# RGB_Matrix.net
KiCad netlist of a schematic drawn in EAGLE
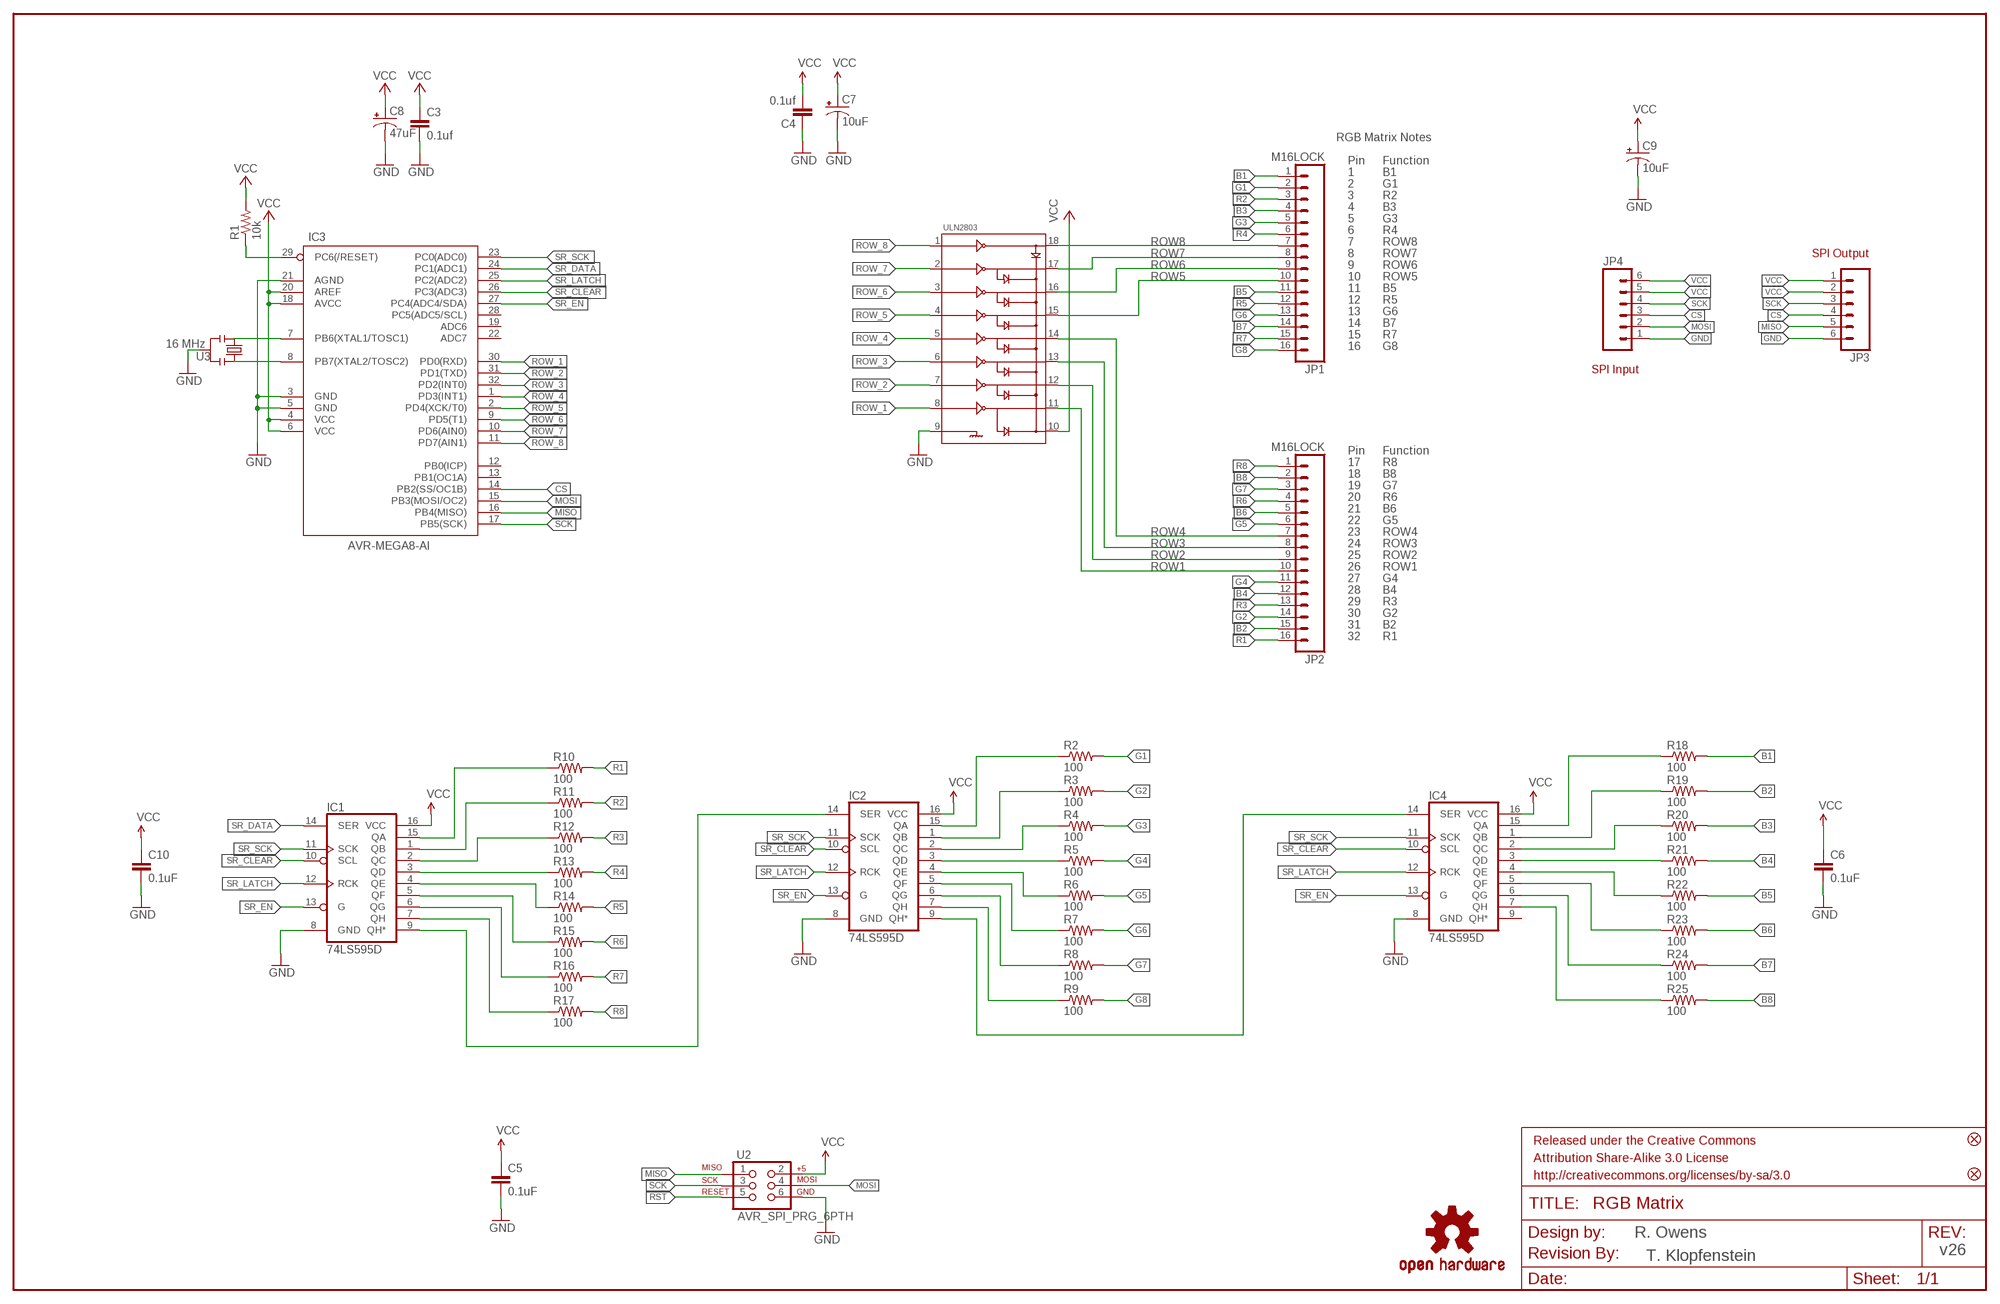
[diagram p0: schematic, sheet 1]

(export (version "E")
  (design (tool "Eeschema 10.0.6"))
  (components
    (comp (ref "C3")
      (value "0.1uf")
      (footprint "eagle-import:0603-CAP")
      (libsource (lib "eagle-import") (part "CAP0603-CAP"))
    )
    (comp (ref "C4")
      (value "0.1uf")
      (footprint "eagle-import:0603-CAP")
      (libsource (lib "eagle-import") (part "CAP0603-CAP"))
    )
    (comp (ref "C5")
      (value "0.1uF")
      (footprint "eagle-import:0603-CAP")
      (libsource (lib "eagle-import") (part "CAP0603-CAP"))
    )
    (comp (ref "C6")
      (value "0.1uF")
      (footprint "eagle-import:0603-CAP")
      (libsource (lib "eagle-import") (part "CAP0603-CAP"))
    )
    (comp (ref "C7")
      (value "10uF")
      (footprint "eagle-import:EIA3216")
      (libsource (lib "eagle-import") (part "CAP_POL1206"))
    )
    (comp (ref "C8")
      (value "47uF")
      (footprint "eagle-import:EIA3528")
      (libsource (lib "eagle-import") (part "CAP_POL3528"))
    )
    (comp (ref "C9")
      (value "10uF")
      (footprint "eagle-import:EIA3216")
      (libsource (lib "eagle-import") (part "CAP_POL1206"))
    )
    (comp (ref "C10")
      (value "0.1uF")
      (footprint "eagle-import:0603-CAP")
      (libsource (lib "eagle-import") (part "CAP0603-CAP"))
    )
    (comp (ref "FRAME1")
      (value "FRAME-LEDGER")
      (footprint "eagle-import:CREATIVE_COMMONS")
      (libsource (lib "eagle-import") (part "FRAME-LEDGER"))
    )
    (comp (ref "IC1")
      (value "74LS595D")
      (footprint "eagle-import:SO16")
      (libsource (lib "eagle-import") (part "74595DLS"))
    )
    (comp (ref "IC2")
      (value "74LS595D")
      (footprint "eagle-import:SO16")
      (libsource (lib "eagle-import") (part "74595DLS"))
    )
    (comp (ref "IC3")
      (value "AVR-MEGA8-AI")
      (footprint "eagle-import:TQFP32-08")
      (libsource (lib "eagle-import") (part "AVR-MEGA8-AI"))
    )
    (comp (ref "IC4")
      (value "74LS595D")
      (footprint "eagle-import:SO16")
      (libsource (lib "eagle-import") (part "74595DLS"))
    )
    (comp (ref "JP1")
      (value "M16LOCK")
      (footprint "eagle-import:1X16_LOCK")
      (libsource (lib "eagle-import") (part "M16LOCK"))
    )
    (comp (ref "JP2")
      (value "M16LOCK")
      (footprint "eagle-import:1X16_LOCK")
      (libsource (lib "eagle-import") (part "M16LOCK"))
    )
    (comp (ref "JP3")
      (value "M06SMD")
      (footprint "eagle-import:1X06-SMD")
      (libsource (lib "eagle-import") (part "M06SMD"))
    )
    (comp (ref "JP4")
      (value "M06LOCK")
      (footprint "eagle-import:1X06_LOCK")
      (libsource (lib "eagle-import") (part "SparkFun-Connectors_M06LOCK"))
    )
    (comp (ref "LOGO1")
      (value "OSHW-LOGOL")
      (footprint "eagle-import:OSHW-LOGO-L")
      (libsource (lib "eagle-import") (part "OSHW-LOGOL"))
    )
    (comp (ref "R1")
      (value "10k")
      (footprint "eagle-import:0603-RES")
      (libsource (lib "eagle-import") (part "RESISTOR0603-RES"))
    )
    (comp (ref "R2")
      (value "100")
      (footprint "eagle-import:0603-RES")
      (libsource (lib "eagle-import") (part "RESISTOR0603-RES"))
    )
    (comp (ref "R3")
      (value "100")
      (footprint "eagle-import:0603-RES")
      (libsource (lib "eagle-import") (part "RESISTOR0603-RES"))
    )
    (comp (ref "R4")
      (value "100")
      (footprint "eagle-import:0603-RES")
      (libsource (lib "eagle-import") (part "RESISTOR0603-RES"))
    )
    (comp (ref "R5")
      (value "100")
      (footprint "eagle-import:0603-RES")
      (libsource (lib "eagle-import") (part "RESISTOR0603-RES"))
    )
    (comp (ref "R6")
      (value "100")
      (footprint "eagle-import:0603-RES")
      (libsource (lib "eagle-import") (part "RESISTOR0603-RES"))
    )
    (comp (ref "R7")
      (value "100")
      (footprint "eagle-import:0603-RES")
      (libsource (lib "eagle-import") (part "RESISTOR0603-RES"))
    )
    (comp (ref "R8")
      (value "100")
      (footprint "eagle-import:0603-RES")
      (libsource (lib "eagle-import") (part "RESISTOR0603-RES"))
    )
    (comp (ref "R9")
      (value "100")
      (footprint "eagle-import:0603-RES")
      (libsource (lib "eagle-import") (part "RESISTOR0603-RES"))
    )
    (comp (ref "R10")
      (value "100")
      (footprint "eagle-import:0603-RES")
      (libsource (lib "eagle-import") (part "RESISTOR0603-RES"))
    )
    (comp (ref "R11")
      (value "100")
      (footprint "eagle-import:0603-RES")
      (libsource (lib "eagle-import") (part "RESISTOR0603-RES"))
    )
    (comp (ref "R12")
      (value "100")
      (footprint "eagle-import:0603-RES")
      (libsource (lib "eagle-import") (part "RESISTOR0603-RES"))
    )
    (comp (ref "R13")
      (value "100")
      (footprint "eagle-import:0603-RES")
      (libsource (lib "eagle-import") (part "RESISTOR0603-RES"))
    )
    (comp (ref "R14")
      (value "100")
      (footprint "eagle-import:0603-RES")
      (libsource (lib "eagle-import") (part "RESISTOR0603-RES"))
    )
    (comp (ref "R15")
      (value "100")
      (footprint "eagle-import:0603-RES")
      (libsource (lib "eagle-import") (part "RESISTOR0603-RES"))
    )
    (comp (ref "R16")
      (value "100")
      (footprint "eagle-import:0603-RES")
      (libsource (lib "eagle-import") (part "RESISTOR0603-RES"))
    )
    (comp (ref "R17")
      (value "100")
      (footprint "eagle-import:0603-RES")
      (libsource (lib "eagle-import") (part "RESISTOR0603-RES"))
    )
    (comp (ref "R18")
      (value "100")
      (footprint "eagle-import:0603-RES")
      (libsource (lib "eagle-import") (part "RESISTOR0603-RES"))
    )
    (comp (ref "R19")
      (value "100")
      (footprint "eagle-import:0603-RES")
      (libsource (lib "eagle-import") (part "RESISTOR0603-RES"))
    )
    (comp (ref "R20")
      (value "100")
      (footprint "eagle-import:0603-RES")
      (libsource (lib "eagle-import") (part "RESISTOR0603-RES"))
    )
    (comp (ref "R21")
      (value "100")
      (footprint "eagle-import:0603-RES")
      (libsource (lib "eagle-import") (part "RESISTOR0603-RES"))
    )
    (comp (ref "R22")
      (value "100")
      (footprint "eagle-import:0603-RES")
      (libsource (lib "eagle-import") (part "RESISTOR0603-RES"))
    )
    (comp (ref "R23")
      (value "100")
      (footprint "eagle-import:0603-RES")
      (libsource (lib "eagle-import") (part "RESISTOR0603-RES"))
    )
    (comp (ref "R24")
      (value "100")
      (footprint "eagle-import:0603-RES")
      (libsource (lib "eagle-import") (part "RESISTOR0603-RES"))
    )
    (comp (ref "R25")
      (value "100")
      (footprint "eagle-import:0603-RES")
      (libsource (lib "eagle-import") (part "RESISTOR0603-RES"))
    )
    (comp (ref "U$1")
      (value "FIDUCIAL1X2")
      (footprint "eagle-import:FIDUCIAL-1X2")
      (libsource (lib "eagle-import") (part "FIDUCIAL1X2"))
    )
    (comp (ref "U$2")
      (value "REVISION")
      (footprint "eagle-import:REVISION")
      (libsource (lib "eagle-import") (part "REVISION"))
    )
    (comp (ref "U$3")
      (value "FIDUCIAL1X2")
      (footprint "eagle-import:FIDUCIAL-1X2")
      (libsource (lib "eagle-import") (part "FIDUCIAL1X2"))
    )
    (comp (ref "U2")
      (value "AVR_SPI_PRG_6PTH")
      (footprint "eagle-import:2X3")
      (libsource (lib "eagle-import") (part "AVR_SPI_PRG_6PTH"))
    )
    (comp (ref "U3")
      (value "16 MHz")
      (footprint "eagle-import:RESONATOR-SMD")
      (libsource (lib "eagle-import") (part "RESONATORSMD"))
    )
    (comp (ref "ULN2803")
      (value "ULN2803SOICW")
      (footprint "eagle-import:SO18L")
      (libsource (lib "eagle-import") (part "ULN2803SOICW"))
    )
  )
  (nets
    (net (code "1") (name "/ROW1") (class "Default")
      (node (ref "JP2") (pin "10") (pinfunction "10_10") (pintype "passive"))
      (node (ref "ULN2803") (pin "11") (pinfunction "11_11") (pintype "bidirectional"))
    )
    (net (code "2") (name "/ROW2") (class "Default")
      (node (ref "JP2") (pin "9") (pinfunction "9_9") (pintype "passive"))
      (node (ref "ULN2803") (pin "12") (pinfunction "12_12") (pintype "bidirectional"))
    )
    (net (code "3") (name "/ROW3") (class "Default")
      (node (ref "JP2") (pin "8") (pinfunction "8_8") (pintype "passive"))
      (node (ref "ULN2803") (pin "13") (pinfunction "13_13") (pintype "bidirectional"))
    )
    (net (code "4") (name "/ROW4") (class "Default")
      (node (ref "JP2") (pin "7") (pinfunction "7_7") (pintype "passive"))
      (node (ref "ULN2803") (pin "14") (pinfunction "14_14") (pintype "bidirectional"))
    )
    (net (code "5") (name "/ROW5") (class "Default")
      (node (ref "JP1") (pin "10") (pinfunction "10_10") (pintype "passive"))
      (node (ref "ULN2803") (pin "15") (pinfunction "15_15") (pintype "bidirectional"))
    )
    (net (code "6") (name "/ROW6") (class "Default")
      (node (ref "JP1") (pin "9") (pinfunction "9_9") (pintype "passive"))
      (node (ref "ULN2803") (pin "16") (pinfunction "16_16") (pintype "bidirectional"))
    )
    (net (code "7") (name "/ROW7") (class "Default")
      (node (ref "JP1") (pin "8") (pinfunction "8_8") (pintype "passive"))
      (node (ref "ULN2803") (pin "17") (pinfunction "17_17") (pintype "bidirectional"))
    )
    (net (code "8") (name "/ROW8") (class "Default")
      (node (ref "JP1") (pin "7") (pinfunction "7_7") (pintype "passive"))
      (node (ref "ULN2803") (pin "18") (pinfunction "18_18") (pintype "bidirectional"))
    )
    (net (code "9") (name "B1") (class "Default")
      (node (ref "JP1") (pin "1") (pinfunction "1_1") (pintype "passive"))
      (node (ref "R18") (pin "2") (pinfunction "2_2") (pintype "passive"))
    )
    (net (code "10") (name "B2") (class "Default")
      (node (ref "JP2") (pin "15") (pinfunction "15_15") (pintype "passive"))
      (node (ref "R19") (pin "2") (pinfunction "2_2") (pintype "passive"))
    )
    (net (code "11") (name "B3") (class "Default")
      (node (ref "JP1") (pin "4") (pinfunction "4_4") (pintype "passive"))
      (node (ref "R20") (pin "2") (pinfunction "2_2") (pintype "passive"))
    )
    (net (code "12") (name "B4") (class "Default")
      (node (ref "JP2") (pin "12") (pinfunction "12_12") (pintype "passive"))
      (node (ref "R21") (pin "2") (pinfunction "2_2") (pintype "passive"))
    )
    (net (code "13") (name "B5") (class "Default")
      (node (ref "JP1") (pin "11") (pinfunction "11_11") (pintype "passive"))
      (node (ref "R22") (pin "2") (pinfunction "2_2") (pintype "passive"))
    )
    (net (code "14") (name "B6") (class "Default")
      (node (ref "JP2") (pin "5") (pinfunction "5_5") (pintype "passive"))
      (node (ref "R23") (pin "2") (pinfunction "2_2") (pintype "passive"))
    )
    (net (code "15") (name "B7") (class "Default")
      (node (ref "JP1") (pin "14") (pinfunction "14_14") (pintype "passive"))
      (node (ref "R24") (pin "2") (pinfunction "2_2") (pintype "passive"))
    )
    (net (code "16") (name "B8") (class "Default")
      (node (ref "JP2") (pin "2") (pinfunction "2_2") (pintype "passive"))
      (node (ref "R25") (pin "2") (pinfunction "2_2") (pintype "passive"))
    )
    (net (code "17") (name "CS") (class "Default")
      (node (ref "IC3") (pin "14") (pinfunction "PB2(SS/OC1B)_14") (pintype "bidirectional"))
      (node (ref "JP3") (pin "4") (pinfunction "4_4") (pintype "passive"))
      (node (ref "JP4") (pin "3") (pinfunction "3_3") (pintype "passive"))
    )
    (net (code "18") (name "G1") (class "Default")
      (node (ref "JP1") (pin "2") (pinfunction "2_2") (pintype "passive"))
      (node (ref "R2") (pin "2") (pinfunction "2_2") (pintype "passive"))
    )
    (net (code "19") (name "G2") (class "Default")
      (node (ref "JP2") (pin "14") (pinfunction "14_14") (pintype "passive"))
      (node (ref "R3") (pin "2") (pinfunction "2_2") (pintype "passive"))
    )
    (net (code "20") (name "G3") (class "Default")
      (node (ref "JP1") (pin "5") (pinfunction "5_5") (pintype "passive"))
      (node (ref "R4") (pin "2") (pinfunction "2_2") (pintype "passive"))
    )
    (net (code "21") (name "G4") (class "Default")
      (node (ref "JP2") (pin "11") (pinfunction "11_11") (pintype "passive"))
      (node (ref "R5") (pin "2") (pinfunction "2_2") (pintype "passive"))
    )
    (net (code "22") (name "G5") (class "Default")
      (node (ref "JP2") (pin "6") (pinfunction "6_6") (pintype "passive"))
      (node (ref "R6") (pin "2") (pinfunction "2_2") (pintype "passive"))
    )
    (net (code "23") (name "G6") (class "Default")
      (node (ref "JP1") (pin "13") (pinfunction "13_13") (pintype "passive"))
      (node (ref "R7") (pin "2") (pinfunction "2_2") (pintype "passive"))
    )
    (net (code "24") (name "G7") (class "Default")
      (node (ref "JP2") (pin "3") (pinfunction "3_3") (pintype "passive"))
      (node (ref "R8") (pin "2") (pinfunction "2_2") (pintype "passive"))
    )
    (net (code "25") (name "G8") (class "Default")
      (node (ref "JP1") (pin "16") (pinfunction "16_16") (pintype "passive"))
      (node (ref "R9") (pin "2") (pinfunction "2_2") (pintype "passive"))
    )
    (net (code "26") (name "GND") (class "Default")
      (node (ref "C10") (pin "2") (pinfunction "2_2") (pintype "passive"))
      (node (ref "C3") (pin "2") (pinfunction "2_2") (pintype "passive"))
      (node (ref "C4") (pin "1") (pinfunction "1_1") (pintype "passive"))
      (node (ref "C5") (pin "2") (pinfunction "2_2") (pintype "passive"))
      (node (ref "C6") (pin "2") (pinfunction "2_2") (pintype "passive"))
      (node (ref "C7") (pin "C") (pinfunction "-_C") (pintype "passive"))
      (node (ref "C8") (pin "C") (pinfunction "-_C") (pintype "passive"))
      (node (ref "C9") (pin "C") (pinfunction "-_C") (pintype "passive"))
      (node (ref "IC1") (pin "8") (pinfunction "GND_8") (pintype "power_in"))
      (node (ref "IC2") (pin "8") (pinfunction "GND_8") (pintype "power_in"))
      (node (ref "IC3") (pin "21") (pinfunction "AGND_21") (pintype "bidirectional"))
      (node (ref "IC3") (pin "3") (pinfunction "GND_3") (pintype "bidirectional"))
      (node (ref "IC3") (pin "5") (pinfunction "GND_5") (pintype "bidirectional"))
      (node (ref "IC4") (pin "8") (pinfunction "GND_8") (pintype "power_in"))
      (node (ref "JP3") (pin "6") (pinfunction "6_6") (pintype "passive"))
      (node (ref "JP4") (pin "1") (pinfunction "1_1") (pintype "passive"))
      (node (ref "U2") (pin "6") (pinfunction "6_6") (pintype "passive"))
      (node (ref "U3") (pin "2") (pinfunction "2_2") (pintype "passive"))
      (node (ref "ULN2803") (pin "9") (pinfunction "9_9") (pintype "bidirectional"))
    )
    (net (code "27") (name "MISO") (class "Default")
      (node (ref "IC3") (pin "16") (pinfunction "PB4(MISO)_16") (pintype "bidirectional"))
      (node (ref "JP3") (pin "5") (pinfunction "5_5") (pintype "passive"))
      (node (ref "U2") (pin "1") (pinfunction "1_1") (pintype "passive"))
    )
    (net (code "28") (name "MOSI") (class "Default")
      (node (ref "IC3") (pin "15") (pinfunction "PB3(MOSI/OC2)_15") (pintype "bidirectional"))
      (node (ref "JP4") (pin "2") (pinfunction "2_2") (pintype "passive"))
      (node (ref "U2") (pin "4") (pinfunction "4_4") (pintype "passive"))
    )
    (net (code "29") (name "Net-(IC1-QA)") (class "Default")
      (node (ref "IC1") (pin "15") (pinfunction "QA_15") (pintype "tri_state"))
      (node (ref "R10") (pin "1") (pinfunction "1_1") (pintype "passive"))
    )
    (net (code "30") (name "Net-(IC1-QB)") (class "Default")
      (node (ref "IC1") (pin "1") (pinfunction "QB_1") (pintype "tri_state"))
      (node (ref "R11") (pin "1") (pinfunction "1_1") (pintype "passive"))
    )
    (net (code "31") (name "Net-(IC1-QC)") (class "Default")
      (node (ref "IC1") (pin "2") (pinfunction "QC_2") (pintype "tri_state"))
      (node (ref "R12") (pin "1") (pinfunction "1_1") (pintype "passive"))
    )
    (net (code "32") (name "Net-(IC1-QD)") (class "Default")
      (node (ref "IC1") (pin "3") (pinfunction "QD_3") (pintype "tri_state"))
      (node (ref "R13") (pin "1") (pinfunction "1_1") (pintype "passive"))
    )
    (net (code "33") (name "Net-(IC1-QE)") (class "Default")
      (node (ref "IC1") (pin "4") (pinfunction "QE_4") (pintype "tri_state"))
      (node (ref "R14") (pin "1") (pinfunction "1_1") (pintype "passive"))
    )
    (net (code "34") (name "Net-(IC1-QF)") (class "Default")
      (node (ref "IC1") (pin "5") (pinfunction "QF_5") (pintype "tri_state"))
      (node (ref "R15") (pin "1") (pinfunction "1_1") (pintype "passive"))
    )
    (net (code "35") (name "Net-(IC1-QG)") (class "Default")
      (node (ref "IC1") (pin "6") (pinfunction "QG_6") (pintype "tri_state"))
      (node (ref "R16") (pin "1") (pinfunction "1_1") (pintype "passive"))
    )
    (net (code "36") (name "Net-(IC1-QH)") (class "Default")
      (node (ref "IC1") (pin "7") (pinfunction "QH_7") (pintype "tri_state"))
      (node (ref "R17") (pin "1") (pinfunction "1_1") (pintype "passive"))
    )
    (net (code "37") (name "Net-(IC1-QH*)") (class "Default")
      (node (ref "IC1") (pin "9") (pinfunction "QH*_9") (pintype "tri_state"))
      (node (ref "IC2") (pin "14") (pinfunction "SER_14") (pintype "input"))
    )
    (net (code "38") (name "Net-(IC2-QA)") (class "Default")
      (node (ref "IC2") (pin "15") (pinfunction "QA_15") (pintype "tri_state"))
      (node (ref "R2") (pin "1") (pinfunction "1_1") (pintype "passive"))
    )
    (net (code "39") (name "Net-(IC2-QB)") (class "Default")
      (node (ref "IC2") (pin "1") (pinfunction "QB_1") (pintype "tri_state"))
      (node (ref "R3") (pin "1") (pinfunction "1_1") (pintype "passive"))
    )
    (net (code "40") (name "Net-(IC2-QC)") (class "Default")
      (node (ref "IC2") (pin "2") (pinfunction "QC_2") (pintype "tri_state"))
      (node (ref "R4") (pin "1") (pinfunction "1_1") (pintype "passive"))
    )
    (net (code "41") (name "Net-(IC2-QD)") (class "Default")
      (node (ref "IC2") (pin "3") (pinfunction "QD_3") (pintype "tri_state"))
      (node (ref "R5") (pin "1") (pinfunction "1_1") (pintype "passive"))
    )
    (net (code "42") (name "Net-(IC2-QE)") (class "Default")
      (node (ref "IC2") (pin "4") (pinfunction "QE_4") (pintype "tri_state"))
      (node (ref "R6") (pin "1") (pinfunction "1_1") (pintype "passive"))
    )
    (net (code "43") (name "Net-(IC2-QF)") (class "Default")
      (node (ref "IC2") (pin "5") (pinfunction "QF_5") (pintype "tri_state"))
      (node (ref "R7") (pin "1") (pinfunction "1_1") (pintype "passive"))
    )
    (net (code "44") (name "Net-(IC2-QG)") (class "Default")
      (node (ref "IC2") (pin "6") (pinfunction "QG_6") (pintype "tri_state"))
      (node (ref "R8") (pin "1") (pinfunction "1_1") (pintype "passive"))
    )
    (net (code "45") (name "Net-(IC2-QH)") (class "Default")
      (node (ref "IC2") (pin "7") (pinfunction "QH_7") (pintype "tri_state"))
      (node (ref "R9") (pin "1") (pinfunction "1_1") (pintype "passive"))
    )
    (net (code "46") (name "Net-(IC2-QH*)") (class "Default")
      (node (ref "IC2") (pin "9") (pinfunction "QH*_9") (pintype "tri_state"))
      (node (ref "IC4") (pin "14") (pinfunction "SER_14") (pintype "input"))
    )
    (net (code "47") (name "Net-(IC3-PB6(XTAL1{slash}TOSC1))") (class "Default")
      (node (ref "IC3") (pin "7") (pinfunction "PB6(XTAL1/TOSC1)_7") (pintype "bidirectional"))
      (node (ref "U3") (pin "1") (pinfunction "1_1") (pintype "passive"))
    )
    (net (code "48") (name "Net-(IC3-PB7(XTAL2{slash}TOSC2))") (class "Default")
      (node (ref "IC3") (pin "8") (pinfunction "PB7(XTAL2/TOSC2)_8") (pintype "bidirectional"))
      (node (ref "U3") (pin "3") (pinfunction "3_3") (pintype "passive"))
    )
    (net (code "49") (name "Net-(IC4-QA)") (class "Default")
      (node (ref "IC4") (pin "15") (pinfunction "QA_15") (pintype "tri_state"))
      (node (ref "R18") (pin "1") (pinfunction "1_1") (pintype "passive"))
    )
    (net (code "50") (name "Net-(IC4-QB)") (class "Default")
      (node (ref "IC4") (pin "1") (pinfunction "QB_1") (pintype "tri_state"))
      (node (ref "R19") (pin "1") (pinfunction "1_1") (pintype "passive"))
    )
    (net (code "51") (name "Net-(IC4-QC)") (class "Default")
      (node (ref "IC4") (pin "2") (pinfunction "QC_2") (pintype "tri_state"))
      (node (ref "R20") (pin "1") (pinfunction "1_1") (pintype "passive"))
    )
    (net (code "52") (name "Net-(IC4-QD)") (class "Default")
      (node (ref "IC4") (pin "3") (pinfunction "QD_3") (pintype "tri_state"))
      (node (ref "R21") (pin "1") (pinfunction "1_1") (pintype "passive"))
    )
    (net (code "53") (name "Net-(IC4-QE)") (class "Default")
      (node (ref "IC4") (pin "4") (pinfunction "QE_4") (pintype "tri_state"))
      (node (ref "R22") (pin "1") (pinfunction "1_1") (pintype "passive"))
    )
    (net (code "54") (name "Net-(IC4-QF)") (class "Default")
      (node (ref "IC4") (pin "5") (pinfunction "QF_5") (pintype "tri_state"))
      (node (ref "R23") (pin "1") (pinfunction "1_1") (pintype "passive"))
    )
    (net (code "55") (name "Net-(IC4-QG)") (class "Default")
      (node (ref "IC4") (pin "6") (pinfunction "QG_6") (pintype "tri_state"))
      (node (ref "R24") (pin "1") (pinfunction "1_1") (pintype "passive"))
    )
    (net (code "56") (name "Net-(IC4-QH)") (class "Default")
      (node (ref "IC4") (pin "7") (pinfunction "QH_7") (pintype "tri_state"))
      (node (ref "R25") (pin "1") (pinfunction "1_1") (pintype "passive"))
    )
    (net (code "57") (name "R1") (class "Default")
      (node (ref "JP2") (pin "16") (pinfunction "16_16") (pintype "passive"))
      (node (ref "R10") (pin "2") (pinfunction "2_2") (pintype "passive"))
    )
    (net (code "58") (name "R2") (class "Default")
      (node (ref "JP1") (pin "3") (pinfunction "3_3") (pintype "passive"))
      (node (ref "R11") (pin "2") (pinfunction "2_2") (pintype "passive"))
    )
    (net (code "59") (name "R3") (class "Default")
      (node (ref "JP2") (pin "13") (pinfunction "13_13") (pintype "passive"))
      (node (ref "R12") (pin "2") (pinfunction "2_2") (pintype "passive"))
    )
    (net (code "60") (name "R4") (class "Default")
      (node (ref "JP1") (pin "6") (pinfunction "6_6") (pintype "passive"))
      (node (ref "R13") (pin "2") (pinfunction "2_2") (pintype "passive"))
    )
    (net (code "61") (name "R5") (class "Default")
      (node (ref "JP1") (pin "12") (pinfunction "12_12") (pintype "passive"))
      (node (ref "R14") (pin "2") (pinfunction "2_2") (pintype "passive"))
    )
    (net (code "62") (name "R6") (class "Default")
      (node (ref "JP2") (pin "4") (pinfunction "4_4") (pintype "passive"))
      (node (ref "R15") (pin "2") (pinfunction "2_2") (pintype "passive"))
    )
    (net (code "63") (name "R7") (class "Default")
      (node (ref "JP1") (pin "15") (pinfunction "15_15") (pintype "passive"))
      (node (ref "R16") (pin "2") (pinfunction "2_2") (pintype "passive"))
    )
    (net (code "64") (name "R8") (class "Default")
      (node (ref "JP2") (pin "1") (pinfunction "1_1") (pintype "passive"))
      (node (ref "R17") (pin "2") (pinfunction "2_2") (pintype "passive"))
    )
    (net (code "65") (name "ROW_1") (class "Default")
      (node (ref "IC3") (pin "30") (pinfunction "PD0(RXD)_30") (pintype "bidirectional"))
      (node (ref "ULN2803") (pin "8") (pinfunction "8_8") (pintype "bidirectional"))
    )
    (net (code "66") (name "ROW_2") (class "Default")
      (node (ref "IC3") (pin "31") (pinfunction "PD1(TXD)_31") (pintype "bidirectional"))
      (node (ref "ULN2803") (pin "7") (pinfunction "7_7") (pintype "bidirectional"))
    )
    (net (code "67") (name "ROW_3") (class "Default")
      (node (ref "IC3") (pin "32") (pinfunction "PD2(INT0)_32") (pintype "bidirectional"))
      (node (ref "ULN2803") (pin "6") (pinfunction "6_6") (pintype "bidirectional"))
    )
    (net (code "68") (name "ROW_4") (class "Default")
      (node (ref "IC3") (pin "1") (pinfunction "PD3(INT1)_1") (pintype "bidirectional"))
      (node (ref "ULN2803") (pin "5") (pinfunction "5_5") (pintype "bidirectional"))
    )
    (net (code "69") (name "ROW_5") (class "Default")
      (node (ref "IC3") (pin "2") (pinfunction "PD4(XCK/T0)_2") (pintype "bidirectional"))
      (node (ref "ULN2803") (pin "4") (pinfunction "4_4") (pintype "bidirectional"))
    )
    (net (code "70") (name "ROW_6") (class "Default")
      (node (ref "IC3") (pin "9") (pinfunction "PD5(T1)_9") (pintype "bidirectional"))
      (node (ref "ULN2803") (pin "3") (pinfunction "3_3") (pintype "bidirectional"))
    )
    (net (code "71") (name "ROW_7") (class "Default")
      (node (ref "IC3") (pin "10") (pinfunction "PD6(AIN0)_10") (pintype "bidirectional"))
      (node (ref "ULN2803") (pin "2") (pinfunction "2_2") (pintype "bidirectional"))
    )
    (net (code "72") (name "ROW_8") (class "Default")
      (node (ref "IC3") (pin "11") (pinfunction "PD7(AIN1)_11") (pintype "bidirectional"))
      (node (ref "ULN2803") (pin "1") (pinfunction "1_1") (pintype "bidirectional"))
    )
    (net (code "73") (name "RST") (class "Default")
      (node (ref "IC3") (pin "29") (pinfunction "PC6(/RESET)_29") (pintype "bidirectional"))
      (node (ref "R1") (pin "1") (pinfunction "1_1") (pintype "passive"))
      (node (ref "U2") (pin "5") (pinfunction "5_5") (pintype "passive"))
    )
    (net (code "74") (name "SCK") (class "Default")
      (node (ref "IC3") (pin "17") (pinfunction "PB5(SCK)_17") (pintype "bidirectional"))
      (node (ref "JP3") (pin "3") (pinfunction "3_3") (pintype "passive"))
      (node (ref "JP4") (pin "4") (pinfunction "4_4") (pintype "passive"))
      (node (ref "U2") (pin "3") (pinfunction "3_3") (pintype "passive"))
    )
    (net (code "75") (name "SR_CLEAR") (class "Default")
      (node (ref "IC1") (pin "10") (pinfunction "SCL_10") (pintype "input"))
      (node (ref "IC2") (pin "10") (pinfunction "SCL_10") (pintype "input"))
      (node (ref "IC3") (pin "26") (pinfunction "PC3(ADC3)_26") (pintype "bidirectional"))
      (node (ref "IC4") (pin "10") (pinfunction "SCL_10") (pintype "input"))
    )
    (net (code "76") (name "SR_DATA") (class "Default")
      (node (ref "IC1") (pin "14") (pinfunction "SER_14") (pintype "input"))
      (node (ref "IC3") (pin "24") (pinfunction "PC1(ADC1)_24") (pintype "bidirectional"))
    )
    (net (code "77") (name "SR_EN") (class "Default")
      (node (ref "IC1") (pin "13") (pinfunction "G_13") (pintype "input"))
      (node (ref "IC2") (pin "13") (pinfunction "G_13") (pintype "input"))
      (node (ref "IC3") (pin "27") (pinfunction "PC4(ADC4/SDA)_27") (pintype "bidirectional"))
      (node (ref "IC4") (pin "13") (pinfunction "G_13") (pintype "input"))
    )
    (net (code "78") (name "SR_LATCH") (class "Default")
      (node (ref "IC1") (pin "12") (pinfunction "RCK_12") (pintype "input"))
      (node (ref "IC2") (pin "12") (pinfunction "RCK_12") (pintype "input"))
      (node (ref "IC3") (pin "25") (pinfunction "PC2(ADC2)_25") (pintype "bidirectional"))
      (node (ref "IC4") (pin "12") (pinfunction "RCK_12") (pintype "input"))
    )
    (net (code "79") (name "SR_SCK") (class "Default")
      (node (ref "IC1") (pin "11") (pinfunction "SCK_11") (pintype "input"))
      (node (ref "IC2") (pin "11") (pinfunction "SCK_11") (pintype "input"))
      (node (ref "IC3") (pin "23") (pinfunction "PC0(ADC0)_23") (pintype "bidirectional"))
      (node (ref "IC4") (pin "11") (pinfunction "SCK_11") (pintype "input"))
    )
    (net (code "80") (name "VCC") (class "Default")
      (node (ref "C10") (pin "1") (pinfunction "1_1") (pintype "passive"))
      (node (ref "C3") (pin "1") (pinfunction "1_1") (pintype "passive"))
      (node (ref "C4") (pin "2") (pinfunction "2_2") (pintype "passive"))
      (node (ref "C5") (pin "1") (pinfunction "1_1") (pintype "passive"))
      (node (ref "C6") (pin "1") (pinfunction "1_1") (pintype "passive"))
      (node (ref "C7") (pin "A") (pinfunction "+_A") (pintype "passive"))
      (node (ref "C8") (pin "A") (pinfunction "+_A") (pintype "passive"))
      (node (ref "C9") (pin "A") (pinfunction "+_A") (pintype "passive"))
      (node (ref "IC1") (pin "16") (pinfunction "VCC_16") (pintype "power_in"))
      (node (ref "IC2") (pin "16") (pinfunction "VCC_16") (pintype "power_in"))
      (node (ref "IC3") (pin "18") (pinfunction "AVCC_18") (pintype "bidirectional"))
      (node (ref "IC3") (pin "20") (pinfunction "AREF_20") (pintype "bidirectional"))
      (node (ref "IC3") (pin "4") (pinfunction "VCC_4") (pintype "bidirectional"))
      (node (ref "IC3") (pin "6") (pinfunction "VCC_6") (pintype "bidirectional"))
      (node (ref "IC4") (pin "16") (pinfunction "VCC_16") (pintype "power_in"))
      (node (ref "JP3") (pin "1") (pinfunction "1_1") (pintype "passive"))
      (node (ref "JP3") (pin "2") (pinfunction "2_2") (pintype "passive"))
      (node (ref "JP4") (pin "5") (pinfunction "5_5") (pintype "passive"))
      (node (ref "JP4") (pin "6") (pinfunction "6_6") (pintype "passive"))
      (node (ref "R1") (pin "2") (pinfunction "2_2") (pintype "passive"))
      (node (ref "U2") (pin "2") (pinfunction "2_2") (pintype "passive"))
      (node (ref "ULN2803") (pin "10") (pinfunction "10_10") (pintype "bidirectional"))
    )
    (net (code "81") (name "unconnected-(IC3-ADC6-Pad19)") (class "Default")
      (node (ref "IC3") (pin "19") (pinfunction "ADC6_19") (pintype "bidirectional"))
    )
    (net (code "82") (name "unconnected-(IC3-ADC7-Pad22)") (class "Default")
      (node (ref "IC3") (pin "22") (pinfunction "ADC7_22") (pintype "bidirectional"))
    )
    (net (code "83") (name "unconnected-(IC3-PB0(ICP)-Pad12)") (class "Default")
      (node (ref "IC3") (pin "12") (pinfunction "PB0(ICP)_12") (pintype "bidirectional"))
    )
    (net (code "84") (name "unconnected-(IC3-PB1(OC1A)-Pad13)") (class "Default")
      (node (ref "IC3") (pin "13") (pinfunction "PB1(OC1A)_13") (pintype "bidirectional"))
    )
    (net (code "85") (name "unconnected-(IC3-PC5(ADC5{slash}SCL)-Pad28)") (class "Default")
      (node (ref "IC3") (pin "28") (pinfunction "PC5(ADC5/SCL)_28") (pintype "bidirectional"))
    )
    (net (code "86") (name "unconnected-(IC4-QH*-Pad9)") (class "Default")
      (node (ref "IC4") (pin "9") (pinfunction "QH*_9") (pintype "tri_state"))
    )
  )
)
